# Ring_Machine.net
KiCad netlist of a schematic drawn in EAGLE
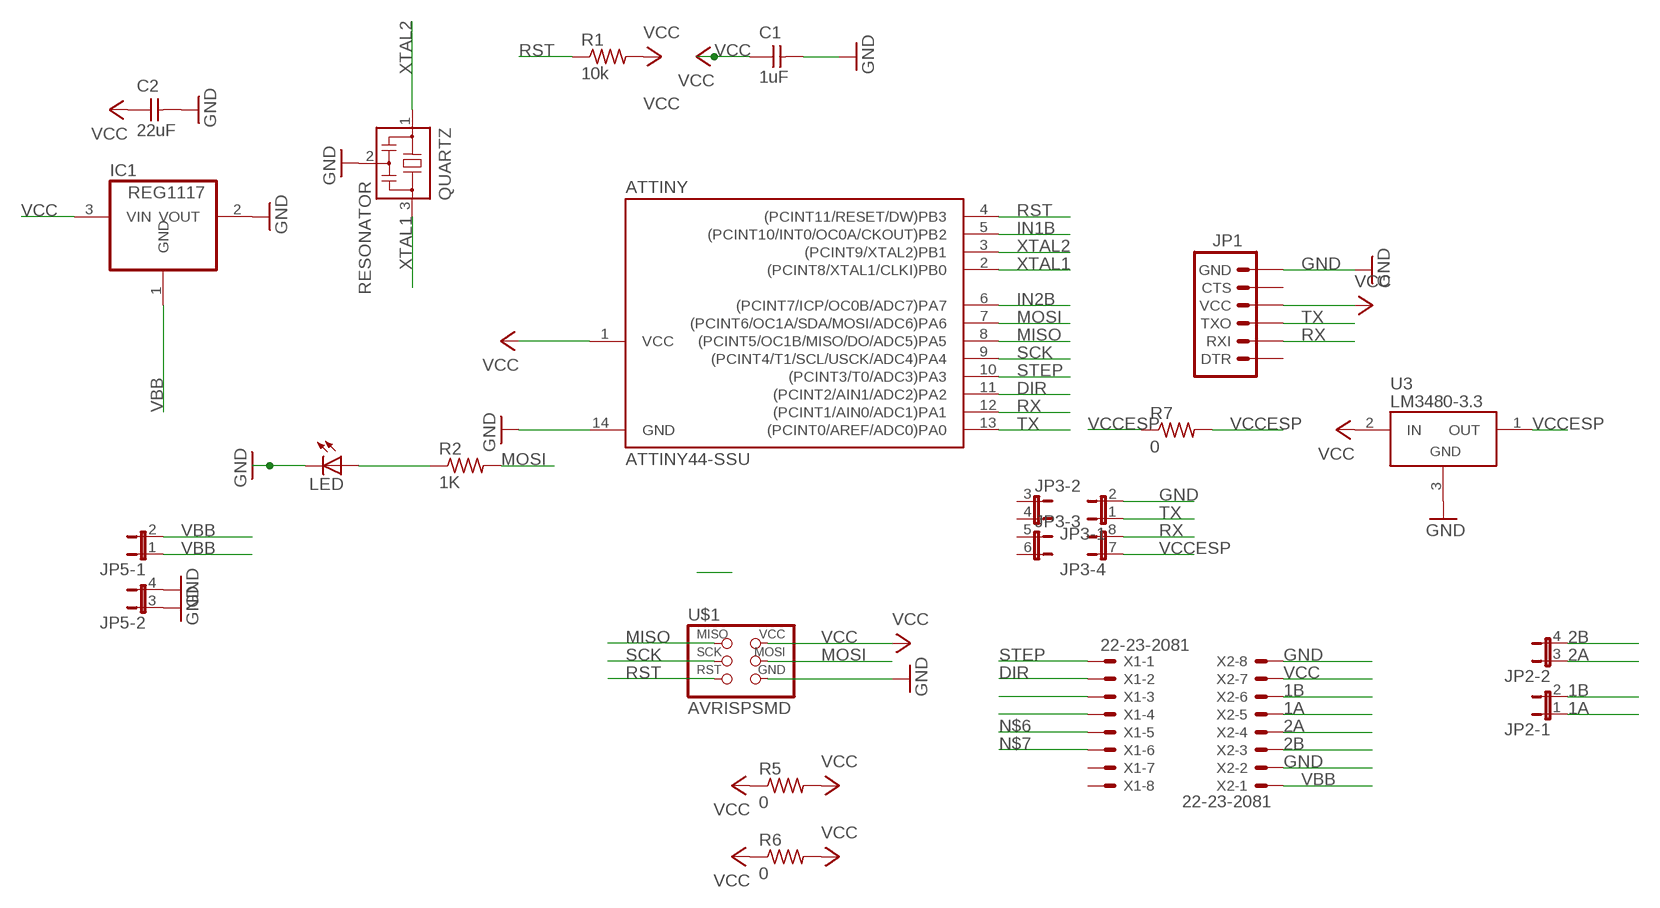
[diagram p0: schematic, sheet 1]

(export (version "E")
  (design (tool "Eeschema 10.0.6"))
  (components
    (comp (ref "ATTINY")
      (value "ATTINY44-SSU")
      (footprint "eagle-import:SOIC14")
      (libsource (lib "eagle-import") (part "ATTINY44-SSU"))
    )
    (comp (ref "C1")
      (value "1uF")
      (footprint "eagle-import:1206")
      (libsource (lib "eagle-import") (part "UNPOLARIZED_CAPACITOR1206"))
    )
    (comp (ref "C2")
      (value "22uF")
      (footprint "eagle-import:1206")
      (libsource (lib "eagle-import") (part "UNPOLARIZED_CAPACITOR1206"))
    )
    (comp (ref "IC1")
      (value "REG1117")
      (footprint "eagle-import:SOT223")
      (libsource (lib "eagle-import") (part "REG1117"))
    )
    (comp (ref "JP1")
      (value "ARDUINO_SERIAL_PROGRAMLONGPADS")
      (footprint "eagle-import:1X06_LONGPADS")
      (libsource (lib "eagle-import") (part "ARDUINO_SERIAL_PROGRAMLONGPADS"))
    )
    (comp (ref "JP2")
      (value "JP2QE")
      (footprint "eagle-import:JP2Q")
      (libsource (lib "eagle-import") (part "JP2QE"))
    )
    (comp (ref "JP3")
      (value "JP4QE")
      (footprint "eagle-import:JP4Q")
      (libsource (lib "eagle-import") (part "JP4QE"))
    )
    (comp (ref "JP5")
      (value "JP2QE")
      (footprint "eagle-import:JP2Q")
      (libsource (lib "eagle-import") (part "JP2QE"))
    )
    (comp (ref "LED")
      (value "LED1206")
      (footprint "eagle-import:1206")
      (libsource (lib "eagle-import") (part "LED1206"))
    )
    (comp (ref "QUARTZ")
      (value "RESONATOR")
      (footprint "eagle-import:EFOBM")
      (libsource (lib "eagle-import") (part "RESONATOR"))
    )
    (comp (ref "R1")
      (value "10k")
      (footprint "eagle-import:1206")
      (libsource (lib "eagle-import") (part "RESISTOR1206"))
    )
    (comp (ref "R2")
      (value "1K")
      (footprint "eagle-import:1206")
      (libsource (lib "eagle-import") (part "RESISTOR1206"))
    )
    (comp (ref "R5")
      (value "0")
      (footprint "eagle-import:1206")
      (libsource (lib "eagle-import") (part "RESISTOR1206"))
    )
    (comp (ref "R6")
      (value "0")
      (footprint "eagle-import:1206")
      (libsource (lib "eagle-import") (part "RESISTOR1206"))
    )
    (comp (ref "R7")
      (value "0")
      (footprint "eagle-import:1206")
      (libsource (lib "eagle-import") (part "RESISTOR1206"))
    )
    (comp (ref "U$1")
      (value "AVRISPSMD")
      (footprint "eagle-import:2X03SMD")
      (libsource (lib "eagle-import") (part "AVRISPSMD"))
    )
    (comp (ref "U3")
      (value "LM3480-3.3")
      (footprint "eagle-import:SOT-23-3")
      (libsource (lib "eagle-import") (part "LM3480-3.3"))
    )
    (comp (ref "X1")
      (value "22-23-2081")
      (footprint "eagle-import:22-23-2081")
      (fields (field (name "MF") "MOLEX"))
      (libsource (lib "eagle-import") (part "22-23-2081"))
    )
    (comp (ref "X2")
      (value "22-23-2081")
      (footprint "eagle-import:22-23-2081")
      (fields (field (name "MF") "MOLEX"))
      (libsource (lib "eagle-import") (part "22-23-2081"))
    )
  )
  (nets
    (net (code "1") (name "/1A") (class "Default")
      (node (ref "JP2") (pin "1") (pinfunction "1_1") (pintype "passive"))
      (node (ref "X2") (pin "5") (pinfunction "S_5") (pintype "passive"))
    )
    (net (code "2") (name "/1B") (class "Default")
      (node (ref "JP2") (pin "2") (pinfunction "2_2") (pintype "passive"))
      (node (ref "X2") (pin "6") (pinfunction "S_6") (pintype "passive"))
    )
    (net (code "3") (name "/2A") (class "Default")
      (node (ref "JP2") (pin "3") (pinfunction "1_3") (pintype "passive"))
      (node (ref "X2") (pin "4") (pinfunction "S_4") (pintype "passive"))
    )
    (net (code "4") (name "/2B") (class "Default")
      (node (ref "JP2") (pin "4") (pinfunction "2_4") (pintype "passive"))
      (node (ref "X2") (pin "3") (pinfunction "S_3") (pintype "passive"))
    )
    (net (code "5") (name "/DIR") (class "Default")
      (node (ref "ATTINY") (pin "11") (pinfunction "(PCINT2/AIN1/ADC2)PA2_11") (pintype "bidirectional"))
      (node (ref "X1") (pin "2") (pinfunction "S_2") (pintype "passive"))
    )
    (net (code "6") (name "/IN1B") (class "Default")
      (node (ref "ATTINY") (pin "5") (pinfunction "(PCINT10/INT0/OC0A/CKOUT)PB2_5") (pintype "bidirectional"))
    )
    (net (code "7") (name "/IN2B") (class "Default")
      (node (ref "ATTINY") (pin "6") (pinfunction "(PCINT7/ICP/OC0B/ADC7)PA7_6") (pintype "bidirectional"))
    )
    (net (code "8") (name "/MISO") (class "Default")
      (node (ref "ATTINY") (pin "8") (pinfunction "(PCINT5/OC1B/MISO/DO/ADC5)PA5_8") (pintype "bidirectional"))
      (node (ref "U$1") (pin "1") (pinfunction "MISO_1") (pintype "passive"))
    )
    (net (code "9") (name "/MOSI") (class "Default")
      (node (ref "ATTINY") (pin "7") (pinfunction "(PCINT6/OC1A/SDA/MOSI/ADC6)PA6_7") (pintype "bidirectional"))
      (node (ref "R2") (pin "2") (pinfunction "2_2") (pintype "passive"))
      (node (ref "U$1") (pin "4") (pinfunction "MOSI_4") (pintype "passive"))
    )
    (net (code "10") (name "/N$6") (class "Default")
      (node (ref "X1") (pin "5") (pinfunction "S_5") (pintype "passive"))
    )
    (net (code "11") (name "/N$7") (class "Default")
      (node (ref "X1") (pin "6") (pinfunction "S_6") (pintype "passive"))
    )
    (net (code "12") (name "/RST") (class "Default")
      (node (ref "ATTINY") (pin "4") (pinfunction "(PCINT11/RESET/DW)PB3_4") (pintype "bidirectional"))
      (node (ref "R1") (pin "1") (pinfunction "1_1") (pintype "passive"))
      (node (ref "U$1") (pin "5") (pinfunction "RST_5") (pintype "passive"))
    )
    (net (code "13") (name "/RX") (class "Default")
      (node (ref "ATTINY") (pin "12") (pinfunction "(PCINT1/AIN0/ADC1)PA1_12") (pintype "bidirectional"))
      (node (ref "JP1") (pin "2") (pinfunction "RXI_2") (pintype "passive"))
      (node (ref "JP3") (pin "8") (pinfunction "2_8") (pintype "passive"))
    )
    (net (code "14") (name "/SCK") (class "Default")
      (node (ref "ATTINY") (pin "9") (pinfunction "(PCINT4/T1/SCL/USCK/ADC4)PA4_9") (pintype "bidirectional"))
      (node (ref "U$1") (pin "3") (pinfunction "SCK_3") (pintype "passive"))
    )
    (net (code "15") (name "/STEP") (class "Default")
      (node (ref "ATTINY") (pin "10") (pinfunction "(PCINT3/T0/ADC3)PA3_10") (pintype "bidirectional"))
      (node (ref "X1") (pin "1") (pinfunction "S_1") (pintype "passive"))
    )
    (net (code "16") (name "/TX") (class "Default")
      (node (ref "ATTINY") (pin "13") (pinfunction "(PCINT0/AREF/ADC0)PA0_13") (pintype "bidirectional"))
      (node (ref "JP1") (pin "3") (pinfunction "TXO_3") (pintype "passive"))
      (node (ref "JP3") (pin "1") (pinfunction "1_1") (pintype "passive"))
    )
    (net (code "17") (name "/VBB") (class "Default")
      (node (ref "IC1") (pin "1") (pinfunction "GND_1") (pintype "power_in"))
      (node (ref "JP5") (pin "1") (pinfunction "1_1") (pintype "passive"))
      (node (ref "JP5") (pin "2") (pinfunction "2_2") (pintype "passive"))
      (node (ref "X2") (pin "1") (pinfunction "S_1") (pintype "passive"))
    )
    (net (code "18") (name "/VCCESP") (class "Default")
      (node (ref "JP3") (pin "7") (pinfunction "1_7") (pintype "passive"))
      (node (ref "R7") (pin "1") (pinfunction "1_1") (pintype "passive"))
      (node (ref "R7") (pin "2") (pinfunction "2_2") (pintype "passive"))
      (node (ref "U3") (pin "1") (pinfunction "OUT_1") (pintype "power_in"))
    )
    (net (code "19") (name "/XTAL1") (class "Default")
      (node (ref "ATTINY") (pin "2") (pinfunction "(PCINT8/XTAL1/CLKI)PB0_2") (pintype "bidirectional"))
      (node (ref "QUARTZ") (pin "3") (pinfunction "3_3") (pintype "passive"))
    )
    (net (code "20") (name "/XTAL2") (class "Default")
      (node (ref "ATTINY") (pin "3") (pinfunction "(PCINT9/XTAL2)PB1_3") (pintype "bidirectional"))
      (node (ref "QUARTZ") (pin "1") (pinfunction "1_1") (pintype "passive"))
    )
    (net (code "21") (name "GND") (class "Default")
      (node (ref "ATTINY") (pin "14") (pinfunction "GND_14") (pintype "power_in"))
      (node (ref "C1") (pin "2") (pinfunction "2_2") (pintype "passive"))
      (node (ref "C2") (pin "2") (pinfunction "2_2") (pintype "passive"))
      (node (ref "IC1") (pin "2") (pinfunction "VOUT_2") (pintype "output"))
      (node (ref "JP1") (pin "6") (pinfunction "GND_6") (pintype "passive"))
      (node (ref "JP3") (pin "2") (pinfunction "2_2") (pintype "passive"))
      (node (ref "JP5") (pin "3") (pinfunction "1_3") (pintype "passive"))
      (node (ref "JP5") (pin "4") (pinfunction "2_4") (pintype "passive"))
      (node (ref "LED") (pin "2") (pinfunction "C_2") (pintype "passive"))
      (node (ref "QUARTZ") (pin "2") (pinfunction "2_2") (pintype "passive"))
      (node (ref "U$1") (pin "6") (pinfunction "GND_6") (pintype "passive"))
      (node (ref "U3") (pin "3") (pinfunction "GND_3") (pintype "power_in"))
      (node (ref "X2") (pin "2") (pinfunction "S_2") (pintype "passive"))
      (node (ref "X2") (pin "8") (pinfunction "S_8") (pintype "passive"))
    )
    (net (code "22") (name "Net-(LED-A)") (class "Default")
      (node (ref "LED") (pin "1") (pinfunction "A_1") (pintype "passive"))
      (node (ref "R2") (pin "1") (pinfunction "1_1") (pintype "passive"))
    )
    (net (code "23") (name "VCC") (class "Default")
      (node (ref "ATTINY") (pin "1") (pinfunction "VCC_1") (pintype "power_in"))
      (node (ref "C1") (pin "1") (pinfunction "1_1") (pintype "passive"))
      (node (ref "C2") (pin "1") (pinfunction "1_1") (pintype "passive"))
      (node (ref "IC1") (pin "3") (pinfunction "VIN_3") (pintype "input"))
      (node (ref "JP1") (pin "4") (pinfunction "VCC_4") (pintype "passive"))
      (node (ref "R1") (pin "2") (pinfunction "2_2") (pintype "passive"))
      (node (ref "R5") (pin "1") (pinfunction "1_1") (pintype "passive"))
      (node (ref "R5") (pin "2") (pinfunction "2_2") (pintype "passive"))
      (node (ref "R6") (pin "1") (pinfunction "1_1") (pintype "passive"))
      (node (ref "R6") (pin "2") (pinfunction "2_2") (pintype "passive"))
      (node (ref "U$1") (pin "2") (pinfunction "VCC_2") (pintype "passive"))
      (node (ref "U3") (pin "2") (pinfunction "IN_2") (pintype "power_in"))
      (node (ref "X2") (pin "7") (pinfunction "S_7") (pintype "passive"))
    )
    (net (code "24") (name "unconnected-(JP1-CTS-Pad5)") (class "Default")
      (node (ref "JP1") (pin "5") (pinfunction "CTS_5") (pintype "passive"))
    )
    (net (code "25") (name "unconnected-(JP1-DTR-Pad1)") (class "Default")
      (node (ref "JP1") (pin "1") (pinfunction "DTR_1") (pintype "passive"))
    )
    (net (code "26") (name "unconnected-(JP3B-1-Pad3)") (class "Default")
      (node (ref "JP3") (pin "3") (pinfunction "1_3") (pintype "passive"))
    )
    (net (code "27") (name "unconnected-(JP3B-2-Pad4)") (class "Default")
      (node (ref "JP3") (pin "4") (pinfunction "2_4") (pintype "passive"))
    )
    (net (code "28") (name "unconnected-(JP3C-1-Pad5)") (class "Default")
      (node (ref "JP3") (pin "5") (pinfunction "1_5") (pintype "passive"))
    )
    (net (code "29") (name "unconnected-(JP3C-2-Pad6)") (class "Default")
      (node (ref "JP3") (pin "6") (pinfunction "2_6") (pintype "passive"))
    )
    (net (code "30") (name "unconnected-(X1C-S-Pad3)") (class "Default")
      (node (ref "X1") (pin "3") (pinfunction "S_3") (pintype "passive"))
    )
    (net (code "31") (name "unconnected-(X1D-S-Pad4)") (class "Default")
      (node (ref "X1") (pin "4") (pinfunction "S_4") (pintype "passive"))
    )
    (net (code "32") (name "unconnected-(X1G-S-Pad7)") (class "Default")
      (node (ref "X1") (pin "7") (pinfunction "S_7") (pintype "passive"))
    )
    (net (code "33") (name "unconnected-(X1H-S-Pad8)") (class "Default")
      (node (ref "X1") (pin "8") (pinfunction "S_8") (pintype "passive"))
    )
  )
)
